# peripherals.net
KiCad netlist of a schematic drawn in Altium Designer
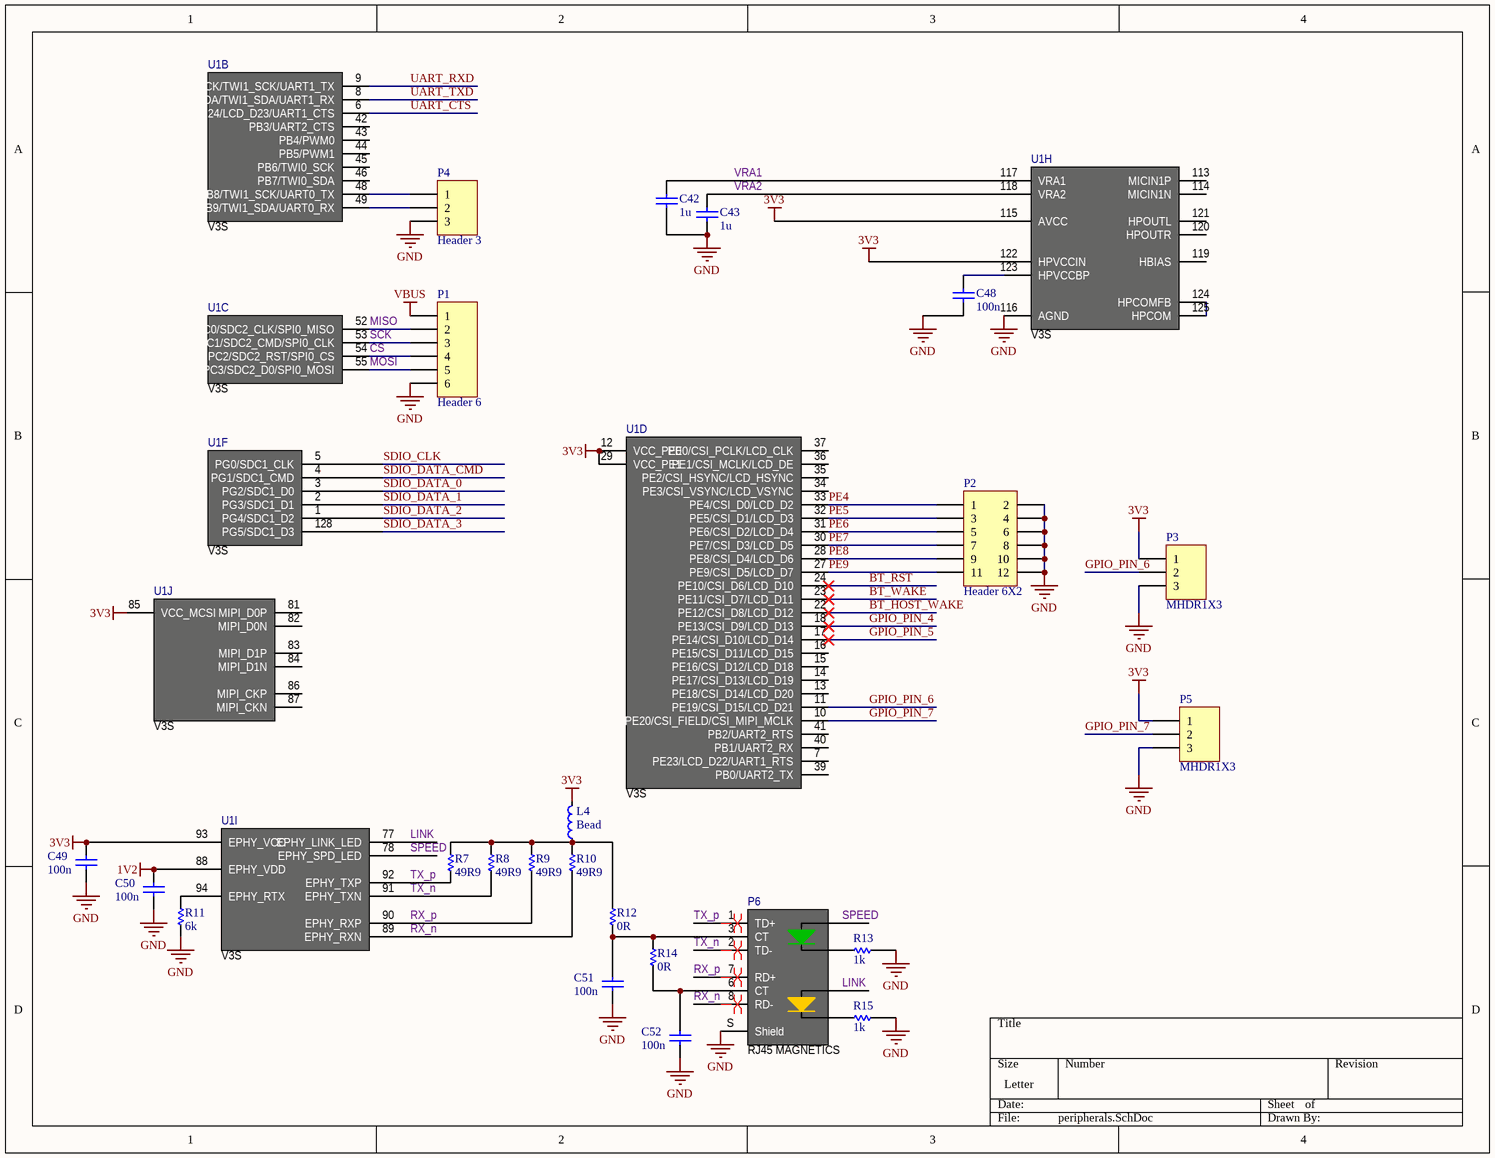
[diagram p0: peripherals.SchDoc]

(export (version "E")
  (design (tool "Eeschema 10.0.6"))
  (components
    (comp (ref "C42")
      (value "1u")
      (footprint "CAPC1005N")
      (description "Capacitor (Semiconductor SIM Model)")
      (fields (field (name "PUBLISHER") "Altium Limited"))
      (libsource (lib "Miscellaneous Devices") (part "Cap Semi"))
    )
    (comp (ref "C43")
      (value "1u")
      (footprint "CAPC1005N")
      (description "Capacitor (Semiconductor SIM Model)")
      (fields (field (name "PUBLISHER") "Altium Limited"))
      (libsource (lib "Miscellaneous Devices") (part "Cap Semi"))
    )
    (comp (ref "C48")
      (value "100n")
      (footprint "CAPC1005N")
      (description "Capacitor (Semiconductor SIM Model)")
      (fields (field (name "PUBLISHER") "Altium Limited"))
      (libsource (lib "Miscellaneous Devices") (part "Cap Semi"))
    )
    (comp (ref "C49")
      (value "100n")
      (footprint "CAPC1005N")
      (description "Capacitor (Semiconductor SIM Model)")
      (fields (field (name "PUBLISHER") "Altium Limited"))
      (libsource (lib "Miscellaneous Devices") (part "Cap Semi"))
    )
    (comp (ref "C50")
      (value "100n")
      (footprint "CAPC1005N")
      (description "Capacitor (Semiconductor SIM Model)")
      (fields (field (name "PUBLISHER") "Altium Limited"))
      (libsource (lib "Miscellaneous Devices") (part "Cap Semi"))
    )
    (comp (ref "C51")
      (value "100n")
      (footprint "CAPC1005N")
      (description "Capacitor (Semiconductor SIM Model)")
      (fields (field (name "PUBLISHER") "Altium Limited"))
      (libsource (lib "Miscellaneous Devices") (part "Cap Semi"))
    )
    (comp (ref "C52")
      (value "100n")
      (footprint "CAPC1005N")
      (description "Capacitor (Semiconductor SIM Model)")
      (fields (field (name "PUBLISHER") "Altium Limited"))
      (libsource (lib "Miscellaneous Devices") (part "Cap Semi"))
    )
    (comp (ref "L4")
      (value "Bead")
      (footprint "INDC1005N")
      (description "Inductor")
      (fields (field (name "PUBLISHER") "Altium Limited"))
      (libsource (lib "Miscellaneous Devices") (part "Inductor"))
    )
    (comp (ref "P1")
      (value "Header 6")
      (footprint "HDR1X6-PINS")
      (description "Header, 6-Pin")
      (fields (field (name "PUBLISHER") "Altium Limited"))
      (libsource (lib "Miscellaneous Connectors") (part "Header 6"))
    )
    (comp (ref "P2")
      (value "Header 6X2")
      (footprint "HDR2X6")
      (description "Header, 6-Pin, Dual row")
      (fields (field (name "PUBLISHER") "Altium Limited"))
      (libsource (lib "Miscellaneous Connectors") (part "Header 6X2"))
    )
    (comp (ref "P3")
      (value "MHDR1X3")
      (footprint "HDR1X3")
      (description "Header, 3-Pin")
      (fields (field (name "PUBLISHER") "Altium Limited"))
      (libsource (lib "Miscellaneous Connectors") (part "MHDR1X3"))
    )
    (comp (ref "P4")
      (value "Header 3")
      (footprint "HDR1X3")
      (description "Header, 3-Pin")
      (fields (field (name "PUBLISHER") "Altium Limited"))
      (libsource (lib "Miscellaneous Connectors") (part "Header 3"))
    )
    (comp (ref "P5")
      (value "MHDR1X3")
      (footprint "HDR1X3")
      (description "Header, 3-Pin")
      (fields (field (name "PUBLISHER") "Altium Limited"))
      (libsource (lib "Miscellaneous Connectors") (part "MHDR1X3"))
    )
    (comp (ref "P6")
      (value "RJ45 MAGNETICS")
      (footprint "ethernet-b")
      (description "RJ-45 Connector with 10/100 Base-TX Magnetics")
      (libsource (lib "Miscellaneous Connectors") (part "Ethernet-B"))
    )
    (comp (ref "R7")
      (value "49R9")
      (footprint "RESC1005N")
      (description "Semiconductor Resistor")
      (fields (field (name "PUBLISHER") "Altium Limited"))
      (libsource (lib "Miscellaneous Devices") (part "Res Semi"))
    )
    (comp (ref "R8")
      (value "49R9")
      (footprint "RESC1005N")
      (description "Semiconductor Resistor")
      (fields (field (name "PUBLISHER") "Altium Limited"))
      (libsource (lib "Miscellaneous Devices") (part "Res Semi"))
    )
    (comp (ref "R9")
      (value "49R9")
      (footprint "RESC1005N")
      (description "Semiconductor Resistor")
      (fields (field (name "PUBLISHER") "Altium Limited"))
      (libsource (lib "Miscellaneous Devices") (part "Res Semi"))
    )
    (comp (ref "R10")
      (value "49R9")
      (footprint "RESC1005N")
      (description "Semiconductor Resistor")
      (fields (field (name "PUBLISHER") "Altium Limited"))
      (libsource (lib "Miscellaneous Devices") (part "Res Semi"))
    )
    (comp (ref "R11")
      (value "6k")
      (footprint "RESC1005N")
      (description "Semiconductor Resistor")
      (fields (field (name "PUBLISHER") "Altium Limited"))
      (libsource (lib "Miscellaneous Devices") (part "Res Semi"))
    )
    (comp (ref "R12")
      (value "0R")
      (footprint "RESC1005N")
      (description "Semiconductor Resistor")
      (fields (field (name "PUBLISHER") "Altium Limited"))
      (libsource (lib "Miscellaneous Devices") (part "Res Semi"))
    )
    (comp (ref "R13")
      (value "1k")
      (footprint "RESC1005N")
      (description "Semiconductor Resistor")
      (fields (field (name "PUBLISHER") "Altium Limited"))
      (libsource (lib "Miscellaneous Devices") (part "Res Semi"))
    )
    (comp (ref "R14")
      (value "0R")
      (footprint "RESC1005N")
      (description "Semiconductor Resistor")
      (fields (field (name "PUBLISHER") "Altium Limited"))
      (libsource (lib "Miscellaneous Devices") (part "Res Semi"))
    )
    (comp (ref "R15")
      (value "1k")
      (footprint "RESC1005N")
      (description "Semiconductor Resistor")
      (fields (field (name "PUBLISHER") "Altium Limited"))
      (libsource (lib "Miscellaneous Devices") (part "Res Semi"))
    )
    (comp (ref "U1") (value "V3S") (footprint "V3S") (libsource (lib "Allwinner SoC") (part "V3S")))
  )
  (nets
    (net (code "1") (name "/BT_HOST_WAKE") (class "Default")
      (node (ref "U1") (pin "22") (pinfunction "PE12/CSI_D8/LCD_D12_22") (pintype "passive+no_connect"))
    )
    (net (code "2") (name "/BT_RST") (class "Default")
      (node (ref "U1") (pin "24") (pinfunction "PE10/CSI_D6/LCD_D10_24") (pintype "passive+no_connect"))
    )
    (net (code "3") (name "/BT_WAKE") (class "Default")
      (node (ref "U1") (pin "23") (pinfunction "PE11/CSI_D7/LCD_D11_23") (pintype "passive+no_connect"))
    )
    (net (code "4") (name "/CS") (class "Default")
      (node (ref "P1") (pin "4") (pinfunction "4_4") (pintype "passive"))
      (node (ref "U1") (pin "54") (pinfunction "PC2/SDC2_RST/SPI0_CS_54") (pintype "passive"))
    )
    (net (code "5") (name "/GPIO_PIN_4") (class "Default")
      (node (ref "U1") (pin "18") (pinfunction "PE13/CSI_D9/LCD_D13_18") (pintype "passive+no_connect"))
    )
    (net (code "6") (name "/GPIO_PIN_5") (class "Default")
      (node (ref "U1") (pin "17") (pinfunction "PE14/CSI_D10/LCD_D14_17") (pintype "passive+no_connect"))
    )
    (net (code "7") (name "/GPIO_PIN_6") (class "Default")
      (node (ref "P3") (pin "2") (pinfunction "2_2") (pintype "passive"))
      (node (ref "U1") (pin "11") (pinfunction "PE19/CSI_D15/LCD_D21_11") (pintype "passive"))
    )
    (net (code "8") (name "/GPIO_PIN_7") (class "Default")
      (node (ref "P5") (pin "2") (pinfunction "2_2") (pintype "passive"))
      (node (ref "U1") (pin "10") (pinfunction "PE20/CSI_FIELD/CSI_MIPI_MCLK_10") (pintype "passive"))
    )
    (net (code "9") (name "/LINK") (class "Default")
      (node (ref "P6") (pin "11") (pintype "passive"))
      (node (ref "U1") (pin "77") (pinfunction "EPHY_LINK_LED_77") (pintype "passive"))
    )
    (net (code "10") (name "/MISO") (class "Default")
      (node (ref "P1") (pin "2") (pinfunction "2_2") (pintype "passive"))
      (node (ref "U1") (pin "52") (pinfunction "PC0/SDC2_CLK/SPI0_MISO_52") (pintype "passive"))
    )
    (net (code "11") (name "/MOSI") (class "Default")
      (node (ref "P1") (pin "5") (pinfunction "5_5") (pintype "passive"))
      (node (ref "U1") (pin "55") (pinfunction "PC3/SDC2_D0/SPI0_MOSI_55") (pintype "passive"))
    )
    (net (code "12") (name "/PE4") (class "Default")
      (node (ref "P2") (pin "1") (pinfunction "1_1") (pintype "passive"))
      (node (ref "U1") (pin "33") (pinfunction "PE4/CSI_D0/LCD_D2_33") (pintype "passive"))
    )
    (net (code "13") (name "/PE5") (class "Default")
      (node (ref "P2") (pin "3") (pinfunction "3_3") (pintype "passive"))
      (node (ref "U1") (pin "32") (pinfunction "PE5/CSI_D1/LCD_D3_32") (pintype "passive"))
    )
    (net (code "14") (name "/PE6") (class "Default")
      (node (ref "P2") (pin "5") (pinfunction "5_5") (pintype "passive"))
      (node (ref "U1") (pin "31") (pinfunction "PE6/CSI_D2/LCD_D4_31") (pintype "passive"))
    )
    (net (code "15") (name "/PE7") (class "Default")
      (node (ref "P2") (pin "7") (pinfunction "7_7") (pintype "passive"))
      (node (ref "U1") (pin "30") (pinfunction "PE7/CSI_D3/LCD_D5_30") (pintype "passive"))
    )
    (net (code "16") (name "/PE8") (class "Default")
      (node (ref "P2") (pin "9") (pinfunction "9_9") (pintype "passive"))
      (node (ref "U1") (pin "28") (pinfunction "PE8/CSI_D4/LCD_D6_28") (pintype "passive"))
    )
    (net (code "17") (name "/PE9") (class "Default")
      (node (ref "P2") (pin "11") (pinfunction "11_11") (pintype "passive"))
      (node (ref "U1") (pin "27") (pinfunction "PE9/CSI_D5/LCD_D7_27") (pintype "passive"))
    )
    (net (code "18") (name "/RX_n") (class "Default")
      (node (ref "P6") (pin "8") (pinfunction "RD-_8") (pintype "passive"))
      (node (ref "R10") (pin "2") (pinfunction "2_2") (pintype "passive"))
      (node (ref "U1") (pin "89") (pinfunction "EPHY_RXN_89") (pintype "passive"))
    )
    (net (code "19") (name "/RX_p") (class "Default")
      (node (ref "P6") (pin "7") (pinfunction "RD+_7") (pintype "passive"))
      (node (ref "R9") (pin "2") (pinfunction "2_2") (pintype "passive"))
      (node (ref "U1") (pin "90") (pinfunction "EPHY_RXP_90") (pintype "passive"))
    )
    (net (code "20") (name "/SCK") (class "Default")
      (node (ref "P1") (pin "3") (pinfunction "3_3") (pintype "passive"))
      (node (ref "U1") (pin "53") (pinfunction "PC1/SDC2_CMD/SPI0_CLK_53") (pintype "passive"))
    )
    (net (code "21") (name "/SDIO_CLK") (class "Default")
      (node (ref "U1") (pin "5") (pinfunction "PG0/SDC1_CLK_5") (pintype "passive"))
    )
    (net (code "22") (name "/SDIO_DATA_0") (class "Default")
      (node (ref "U1") (pin "3") (pinfunction "PG2/SDC1_D0_3") (pintype "passive"))
    )
    (net (code "23") (name "/SDIO_DATA_1") (class "Default")
      (node (ref "U1") (pin "2") (pinfunction "PG3/SDC1_D1_2") (pintype "passive"))
    )
    (net (code "24") (name "/SDIO_DATA_2") (class "Default")
      (node (ref "U1") (pin "1") (pinfunction "PG4/SDC1_D2_1") (pintype "passive"))
    )
    (net (code "25") (name "/SDIO_DATA_3") (class "Default")
      (node (ref "U1") (pin "128") (pinfunction "PG5/SDC1_D3_128") (pintype "passive"))
    )
    (net (code "26") (name "/SDIO_DATA_CMD") (class "Default")
      (node (ref "U1") (pin "4") (pinfunction "PG1/SDC1_CMD_4") (pintype "passive"))
    )
    (net (code "27") (name "/SPEED") (class "Default")
      (node (ref "P6") (pin "9") (pintype "passive"))
      (node (ref "U1") (pin "78") (pinfunction "EPHY_SPD_LED_78") (pintype "passive"))
    )
    (net (code "28") (name "/TX_n") (class "Default")
      (node (ref "P6") (pin "2") (pinfunction "TD-_2") (pintype "passive"))
      (node (ref "R8") (pin "2") (pinfunction "2_2") (pintype "passive"))
      (node (ref "U1") (pin "91") (pinfunction "EPHY_TXN_91") (pintype "passive"))
    )
    (net (code "29") (name "/TX_p") (class "Default")
      (node (ref "P6") (pin "1") (pinfunction "TD+_1") (pintype "passive"))
      (node (ref "R7") (pin "2") (pinfunction "2_2") (pintype "passive"))
      (node (ref "U1") (pin "92") (pinfunction "EPHY_TXP_92") (pintype "passive"))
    )
    (net (code "30") (name "/UART_CTS") (class "Default")
      (node (ref "U1") (pin "6") (pinfunction "PE24/LCD_D23/UART1_CTS_6") (pintype "passive"))
    )
    (net (code "31") (name "/UART_RXD") (class "Default")
      (node (ref "U1") (pin "9") (pinfunction "PE21/CSI_SCK/TWI1_SCK/UART1_TX_9") (pintype "passive"))
    )
    (net (code "32") (name "/UART_TXD") (class "Default")
      (node (ref "U1") (pin "8") (pinfunction "PE22/CSI_SDA/TWI1_SDA/UART1_RX_8") (pintype "passive"))
    )
    (net (code "33") (name "/VRA1") (class "Default")
      (node (ref "C42") (pin "2") (pinfunction "2_2") (pintype "passive"))
      (node (ref "U1") (pin "117") (pinfunction "VRA1_117") (pintype "passive"))
    )
    (net (code "34") (name "/VRA2") (class "Default")
      (node (ref "C43") (pin "2") (pinfunction "2_2") (pintype "passive"))
      (node (ref "U1") (pin "118") (pinfunction "VRA2_118") (pintype "passive"))
    )
    (net (code "35") (name "1V2") (class "Default")
      (node (ref "C50") (pin "2") (pinfunction "2_2") (pintype "passive"))
      (node (ref "U1") (pin "88") (pinfunction "EPHY_VDD_88") (pintype "passive"))
    )
    (net (code "36") (name "3V3") (class "Default")
      (node (ref "C49") (pin "2") (pinfunction "2_2") (pintype "passive"))
      (node (ref "L4") (pin "2") (pinfunction "2_2") (pintype "passive"))
      (node (ref "P3") (pin "1") (pinfunction "1_1") (pintype "passive"))
      (node (ref "P5") (pin "1") (pinfunction "1_1") (pintype "passive"))
      (node (ref "U1") (pin "115") (pinfunction "AVCC_115") (pintype "passive"))
      (node (ref "U1") (pin "12") (pinfunction "VCC_PE0_12") (pintype "passive"))
      (node (ref "U1") (pin "122") (pinfunction "HPVCCIN_122") (pintype "passive"))
      (node (ref "U1") (pin "29") (pinfunction "VCC_PE1_29") (pintype "passive"))
      (node (ref "U1") (pin "85") (pinfunction "VCC_MCSI_85") (pintype "passive"))
      (node (ref "U1") (pin "93") (pinfunction "EPHY_VCC_93") (pintype "passive"))
    )
    (net (code "37") (name "GND") (class "Default")
      (node (ref "C42") (pin "1") (pinfunction "1_1") (pintype "passive"))
      (node (ref "C43") (pin "1") (pinfunction "1_1") (pintype "passive"))
      (node (ref "C48") (pin "1") (pinfunction "1_1") (pintype "passive"))
      (node (ref "C49") (pin "1") (pinfunction "1_1") (pintype "passive"))
      (node (ref "C50") (pin "1") (pinfunction "1_1") (pintype "passive"))
      (node (ref "C51") (pin "1") (pinfunction "1_1") (pintype "passive"))
      (node (ref "C52") (pin "1") (pinfunction "1_1") (pintype "passive"))
      (node (ref "P1") (pin "6") (pinfunction "6_6") (pintype "passive"))
      (node (ref "P2") (pin "10") (pinfunction "10_10") (pintype "passive"))
      (node (ref "P2") (pin "12") (pinfunction "12_12") (pintype "passive"))
      (node (ref "P2") (pin "2") (pinfunction "2_2") (pintype "passive"))
      (node (ref "P2") (pin "4") (pinfunction "4_4") (pintype "passive"))
      (node (ref "P2") (pin "6") (pinfunction "6_6") (pintype "passive"))
      (node (ref "P2") (pin "8") (pinfunction "8_8") (pintype "passive"))
      (node (ref "P3") (pin "3") (pinfunction "3_3") (pintype "passive"))
      (node (ref "P4") (pin "3") (pinfunction "3_3") (pintype "passive"))
      (node (ref "P5") (pin "3") (pinfunction "3_3") (pintype "passive"))
      (node (ref "P6") (pin "S") (pinfunction "Shield_S") (pintype "passive"))
      (node (ref "R11") (pin "1") (pinfunction "1_1") (pintype "passive"))
      (node (ref "R13") (pin "1") (pinfunction "1_1") (pintype "passive"))
      (node (ref "R15") (pin "1") (pinfunction "1_1") (pintype "passive"))
      (node (ref "U1") (pin "116") (pinfunction "AGND_116") (pintype "passive"))
    )
    (net (code "38") (name "Net-(C51-Pad2)") (class "Default")
      (node (ref "C51") (pin "2") (pinfunction "2_2") (pintype "passive"))
      (node (ref "P6") (pin "3") (pinfunction "CT_3") (pintype "passive"))
      (node (ref "R12") (pin "1") (pinfunction "1_1") (pintype "passive"))
      (node (ref "R14") (pin "2") (pinfunction "2_2") (pintype "passive"))
    )
    (net (code "39") (name "Net-(C52-Pad2)") (class "Default")
      (node (ref "C52") (pin "2") (pinfunction "2_2") (pintype "passive"))
      (node (ref "P6") (pin "6") (pinfunction "CT_6") (pintype "passive"))
      (node (ref "R14") (pin "1") (pinfunction "1_1") (pintype "passive"))
    )
    (net (code "40") (name "Net-(L4-Pad1)") (class "Default")
      (node (ref "L4") (pin "1") (pinfunction "1_1") (pintype "passive"))
      (node (ref "R10") (pin "1") (pinfunction "1_1") (pintype "passive"))
      (node (ref "R12") (pin "2") (pinfunction "2_2") (pintype "passive"))
      (node (ref "R7") (pin "1") (pinfunction "1_1") (pintype "passive"))
      (node (ref "R8") (pin "1") (pinfunction "1_1") (pintype "passive"))
      (node (ref "R9") (pin "1") (pinfunction "1_1") (pintype "passive"))
    )
    (net (code "41") (name "Net-(P6-Pad10)") (class "Default")
      (node (ref "P6") (pin "10") (pintype "passive"))
      (node (ref "R13") (pin "2") (pinfunction "2_2") (pintype "passive"))
    )
    (net (code "42") (name "Net-(P6-Pad12)") (class "Default")
      (node (ref "P6") (pin "12") (pintype "passive"))
      (node (ref "R15") (pin "2") (pinfunction "2_2") (pintype "passive"))
    )
    (net (code "43") (name "Net-(U1B-PB8{slash}TWI1_SCK{slash}UART0_TX)") (class "Default")
      (node (ref "P4") (pin "1") (pinfunction "1_1") (pintype "passive"))
      (node (ref "U1") (pin "48") (pinfunction "PB8/TWI1_SCK/UART0_TX_48") (pintype "passive"))
    )
    (net (code "44") (name "Net-(U1B-PB9{slash}TWI1_SDA{slash}UART0_RX)") (class "Default")
      (node (ref "P4") (pin "2") (pinfunction "2_2") (pintype "passive"))
      (node (ref "U1") (pin "49") (pinfunction "PB9/TWI1_SDA/UART0_RX_49") (pintype "passive"))
    )
    (net (code "45") (name "Net-(U1H-HPCOM)") (class "Default")
      (node (ref "U1") (pin "124") (pinfunction "HPCOMFB_124") (pintype "passive"))
      (node (ref "U1") (pin "125") (pinfunction "HPCOM_125") (pintype "passive"))
    )
    (net (code "46") (name "Net-(U1H-HPVCCBP)") (class "Default")
      (node (ref "C48") (pin "2") (pinfunction "2_2") (pintype "passive"))
      (node (ref "U1") (pin "123") (pinfunction "HPVCCBP_123") (pintype "passive"))
    )
    (net (code "47") (name "Net-(U1I-EPHY_RTX)") (class "Default")
      (node (ref "R11") (pin "2") (pinfunction "2_2") (pintype "passive"))
      (node (ref "U1") (pin "94") (pinfunction "EPHY_RTX_94") (pintype "passive"))
    )
    (net (code "48") (name "VBUS") (class "Default")
      (node (ref "P1") (pin "1") (pinfunction "1_1") (pintype "passive"))
    )
    (net (code "49") (name "unconnected-(U1B-PB3{slash}UART2_CTS-Pad42)") (class "Default")
      (node (ref "U1") (pin "42") (pinfunction "PB3/UART2_CTS_42") (pintype "passive"))
    )
    (net (code "50") (name "unconnected-(U1B-PB4{slash}PWM0-Pad43)") (class "Default")
      (node (ref "U1") (pin "43") (pinfunction "PB4/PWM0_43") (pintype "passive"))
    )
    (net (code "51") (name "unconnected-(U1B-PB5{slash}PWM1-Pad44)") (class "Default")
      (node (ref "U1") (pin "44") (pinfunction "PB5/PWM1_44") (pintype "passive"))
    )
    (net (code "52") (name "unconnected-(U1B-PB6{slash}TWI0_SCK-Pad45)") (class "Default")
      (node (ref "U1") (pin "45") (pinfunction "PB6/TWI0_SCK_45") (pintype "passive"))
    )
    (net (code "53") (name "unconnected-(U1B-PB7{slash}TWI0_SDA-Pad46)") (class "Default")
      (node (ref "U1") (pin "46") (pinfunction "PB7/TWI0_SDA_46") (pintype "passive"))
    )
    (net (code "54") (name "unconnected-(U1D-PB0{slash}UART2_TX-Pad39)") (class "Default")
      (node (ref "U1") (pin "39") (pinfunction "PB0/UART2_TX_39") (pintype "passive"))
    )
    (net (code "55") (name "unconnected-(U1D-PB1{slash}UART2_RX-Pad40)") (class "Default")
      (node (ref "U1") (pin "40") (pinfunction "PB1/UART2_RX_40") (pintype "passive"))
    )
    (net (code "56") (name "unconnected-(U1D-PB2{slash}UART2_RTS-Pad41)") (class "Default")
      (node (ref "U1") (pin "41") (pinfunction "PB2/UART2_RTS_41") (pintype "passive"))
    )
    (net (code "57") (name "unconnected-(U1D-PE0{slash}CSI_PCLK{slash}LCD_CLK-Pad37)") (class "Default")
      (node (ref "U1") (pin "37") (pinfunction "PE0/CSI_PCLK/LCD_CLK_37") (pintype "passive"))
    )
    (net (code "58") (name "unconnected-(U1D-PE1{slash}CSI_MCLK{slash}LCD_DE-Pad36)") (class "Default")
      (node (ref "U1") (pin "36") (pinfunction "PE1/CSI_MCLK/LCD_DE_36") (pintype "passive"))
    )
    (net (code "59") (name "unconnected-(U1D-PE2{slash}CSI_HSYNC{slash}LCD_HSYNC-Pad35)") (class "Default")
      (node (ref "U1") (pin "35") (pinfunction "PE2/CSI_HSYNC/LCD_HSYNC_35") (pintype "passive"))
    )
    (net (code "60") (name "unconnected-(U1D-PE3{slash}CSI_VSYNC{slash}LCD_VSYNC-Pad34)") (class "Default")
      (node (ref "U1") (pin "34") (pinfunction "PE3/CSI_VSYNC/LCD_VSYNC_34") (pintype "passive"))
    )
    (net (code "61") (name "unconnected-(U1D-PE15{slash}CSI_D11{slash}LCD_D15-Pad16)") (class "Default")
      (node (ref "U1") (pin "16") (pinfunction "PE15/CSI_D11/LCD_D15_16") (pintype "passive"))
    )
    (net (code "62") (name "unconnected-(U1D-PE16{slash}CSI_D12{slash}LCD_D18-Pad15)") (class "Default")
      (node (ref "U1") (pin "15") (pinfunction "PE16/CSI_D12/LCD_D18_15") (pintype "passive"))
    )
    (net (code "63") (name "unconnected-(U1D-PE17{slash}CSI_D13{slash}LCD_D19-Pad14)") (class "Default")
      (node (ref "U1") (pin "14") (pinfunction "PE17/CSI_D13/LCD_D19_14") (pintype "passive"))
    )
    (net (code "64") (name "unconnected-(U1D-PE18{slash}CSI_D14{slash}LCD_D20-Pad13)") (class "Default")
      (node (ref "U1") (pin "13") (pinfunction "PE18/CSI_D14/LCD_D20_13") (pintype "passive"))
    )
    (net (code "65") (name "unconnected-(U1D-PE23{slash}LCD_D22{slash}UART1_RTS-Pad7)") (class "Default")
      (node (ref "U1") (pin "7") (pinfunction "PE23/LCD_D22/UART1_RTS_7") (pintype "passive"))
    )
    (net (code "66") (name "unconnected-(U1H-HBIAS-Pad119)") (class "Default")
      (node (ref "U1") (pin "119") (pinfunction "HBIAS_119") (pintype "passive"))
    )
    (net (code "67") (name "unconnected-(U1H-HPOUTL-Pad121)") (class "Default")
      (node (ref "U1") (pin "121") (pinfunction "HPOUTL_121") (pintype "passive"))
    )
    (net (code "68") (name "unconnected-(U1H-HPOUTR-Pad120)") (class "Default")
      (node (ref "U1") (pin "120") (pinfunction "HPOUTR_120") (pintype "passive"))
    )
    (net (code "69") (name "unconnected-(U1H-MICIN1N-Pad114)") (class "Default")
      (node (ref "U1") (pin "114") (pinfunction "MICIN1N_114") (pintype "passive"))
    )
    (net (code "70") (name "unconnected-(U1H-MICIN1P-Pad113)") (class "Default")
      (node (ref "U1") (pin "113") (pinfunction "MICIN1P_113") (pintype "passive"))
    )
    (net (code "71") (name "unconnected-(U1J-MIPI_CKN-Pad87)") (class "Default")
      (node (ref "U1") (pin "87") (pinfunction "MIPI_CKN_87") (pintype "passive"))
    )
    (net (code "72") (name "unconnected-(U1J-MIPI_CKP-Pad86)") (class "Default")
      (node (ref "U1") (pin "86") (pinfunction "MIPI_CKP_86") (pintype "passive"))
    )
    (net (code "73") (name "unconnected-(U1J-MIPI_D0N-Pad82)") (class "Default")
      (node (ref "U1") (pin "82") (pinfunction "MIPI_D0N_82") (pintype "passive"))
    )
    (net (code "74") (name "unconnected-(U1J-MIPI_D0P-Pad81)") (class "Default")
      (node (ref "U1") (pin "81") (pinfunction "MIPI_D0P_81") (pintype "passive"))
    )
    (net (code "75") (name "unconnected-(U1J-MIPI_D1N-Pad84)") (class "Default")
      (node (ref "U1") (pin "84") (pinfunction "MIPI_D1N_84") (pintype "passive"))
    )
    (net (code "76") (name "unconnected-(U1J-MIPI_D1P-Pad83)") (class "Default")
      (node (ref "U1") (pin "83") (pinfunction "MIPI_D1P_83") (pintype "passive"))
    )
  )
)
